# Main.net
KiCad netlist of a schematic drawn in EAGLE
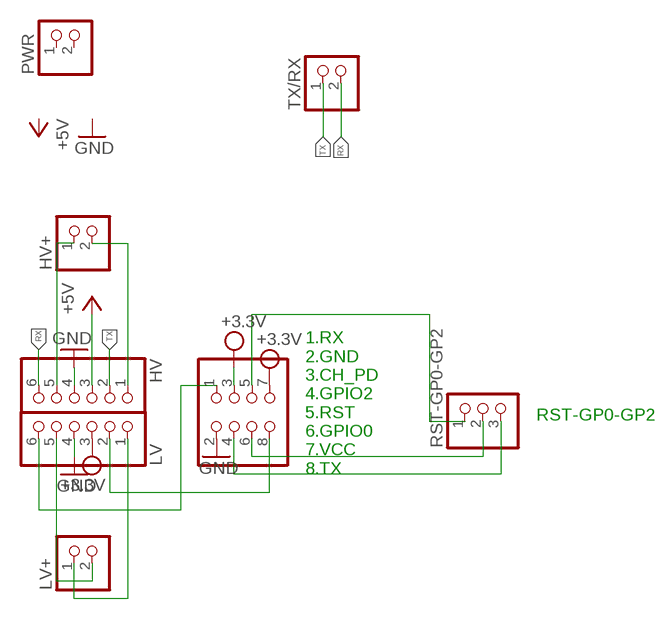
[diagram p0: schematic, sheet 1]

(export (version "E")
  (design (tool "Eeschema 10.0.6"))
  (components
    (comp (ref "HV")
      (value "PINHD-1X6")
      (footprint "eagle-import:1X06")
      (libsource (lib "eagle-import") (part "PINHD-1X6"))
    )
    (comp (ref "HV+")
      (value "PINHD-1X2")
      (footprint "eagle-import:1X02")
      (libsource (lib "eagle-import") (part "PINHD-1X2"))
    )
    (comp (ref "LV")
      (value "PINHD-1X6")
      (footprint "eagle-import:1X06")
      (libsource (lib "eagle-import") (part "PINHD-1X6"))
    )
    (comp (ref "LV+")
      (value "PINHD-1X2")
      (footprint "eagle-import:1X02")
      (libsource (lib "eagle-import") (part "PINHD-1X2"))
    )
    (comp (ref "PWR")
      (value "PINHD-1X2")
      (footprint "eagle-import:1X02")
      (libsource (lib "eagle-import") (part "PINHD-1X2"))
    )
    (comp (ref "RST-GP0-GP2")
      (value "PINHD-1X3")
      (footprint "eagle-import:1X03")
      (libsource (lib "eagle-import") (part "PINHD-1X3"))
    )
    (comp (ref "SOCLU_ESP")
      (value "PINHD-2X4")
      (footprint "eagle-import:2X04")
      (libsource (lib "eagle-import") (part "PINHD-2X4"))
    )
    (comp (ref "TX/RX")
      (value "PINHD-1X2")
      (footprint "eagle-import:1X02")
      (libsource (lib "eagle-import") (part "PINHD-1X2"))
    )
  )
  (nets
    (net (code "1") (name "+3.3V") (class "Default")
      (node (ref "LV") (pin "3") (pinfunction "3_3") (pintype "passive"))
      (node (ref "SOCLU_ESP") (pin "3") (pinfunction "3_3") (pintype "passive"))
      (node (ref "SOCLU_ESP") (pin "7") (pinfunction "7_7") (pintype "passive"))
    )
    (net (code "2") (name "+5V") (class "Default")
      (node (ref "HV") (pin "3") (pinfunction "3_3") (pintype "passive"))
    )
    (net (code "3") (name "GND") (class "Default")
      (node (ref "HV") (pin "4") (pinfunction "4_4") (pintype "passive"))
      (node (ref "LV") (pin "4") (pinfunction "4_4") (pintype "passive"))
      (node (ref "SOCLU_ESP") (pin "2") (pinfunction "2_2") (pintype "passive"))
    )
    (net (code "4") (name "Net-(HV+-Pad1)") (class "Default")
      (node (ref "HV") (pin "5") (pinfunction "5_5") (pintype "passive"))
      (node (ref "HV+") (pin "1") (pinfunction "1_1") (pintype "passive"))
    )
    (net (code "5") (name "Net-(HV+-Pad2)") (class "Default")
      (node (ref "HV") (pin "1") (pinfunction "1_1") (pintype "passive"))
      (node (ref "HV+") (pin "2") (pinfunction "2_2") (pintype "passive"))
    )
    (net (code "6") (name "Net-(LV+-Pad1)") (class "Default")
      (node (ref "LV") (pin "1") (pinfunction "1_1") (pintype "passive"))
      (node (ref "LV+") (pin "1") (pinfunction "1_1") (pintype "passive"))
    )
    (net (code "7") (name "Net-(LV+-Pad2)") (class "Default")
      (node (ref "LV") (pin "5") (pinfunction "5_5") (pintype "passive"))
      (node (ref "LV+") (pin "2") (pinfunction "2_2") (pintype "passive"))
    )
    (net (code "8") (name "Net-(LV-Pad2)") (class "Default")
      (node (ref "LV") (pin "2") (pinfunction "2_2") (pintype "passive"))
      (node (ref "SOCLU_ESP") (pin "8") (pinfunction "8_8") (pintype "passive"))
    )
    (net (code "9") (name "Net-(LV-Pad6)") (class "Default")
      (node (ref "LV") (pin "6") (pinfunction "6_6") (pintype "passive"))
      (node (ref "SOCLU_ESP") (pin "1") (pinfunction "1_1") (pintype "passive"))
    )
    (net (code "10") (name "Net-(RST-GP0-GP2-Pad1)") (class "Default")
      (node (ref "RST-GP0-GP2") (pin "1") (pinfunction "1_1") (pintype "passive"))
      (node (ref "SOCLU_ESP") (pin "5") (pinfunction "5_5") (pintype "passive"))
    )
    (net (code "11") (name "Net-(RST-GP0-GP2-Pad2)") (class "Default")
      (node (ref "RST-GP0-GP2") (pin "2") (pinfunction "2_2") (pintype "passive"))
      (node (ref "SOCLU_ESP") (pin "6") (pinfunction "6_6") (pintype "passive"))
    )
    (net (code "12") (name "Net-(RST-GP0-GP2-Pad3)") (class "Default")
      (node (ref "RST-GP0-GP2") (pin "3") (pinfunction "3_3") (pintype "passive"))
      (node (ref "SOCLU_ESP") (pin "4") (pinfunction "4_4") (pintype "passive"))
    )
    (net (code "13") (name "RX") (class "Default")
      (node (ref "HV") (pin "6") (pinfunction "6_6") (pintype "passive"))
      (node (ref "TX/RX") (pin "2") (pinfunction "2_2") (pintype "passive"))
    )
    (net (code "14") (name "TX") (class "Default")
      (node (ref "HV") (pin "2") (pinfunction "2_2") (pintype "passive"))
      (node (ref "TX/RX") (pin "1") (pinfunction "1_1") (pintype "passive"))
    )
    (net (code "15") (name "unconnected-(PWR-Pad1)") (class "Default")
      (node (ref "PWR") (pin "1") (pinfunction "1_1") (pintype "passive"))
    )
    (net (code "16") (name "unconnected-(PWR-Pad2)") (class "Default")
      (node (ref "PWR") (pin "2") (pinfunction "2_2") (pintype "passive"))
    )
  )
)
